# dual_encoder_i2c_revD.net
KiCad netlist of a schematic drawn in EAGLE
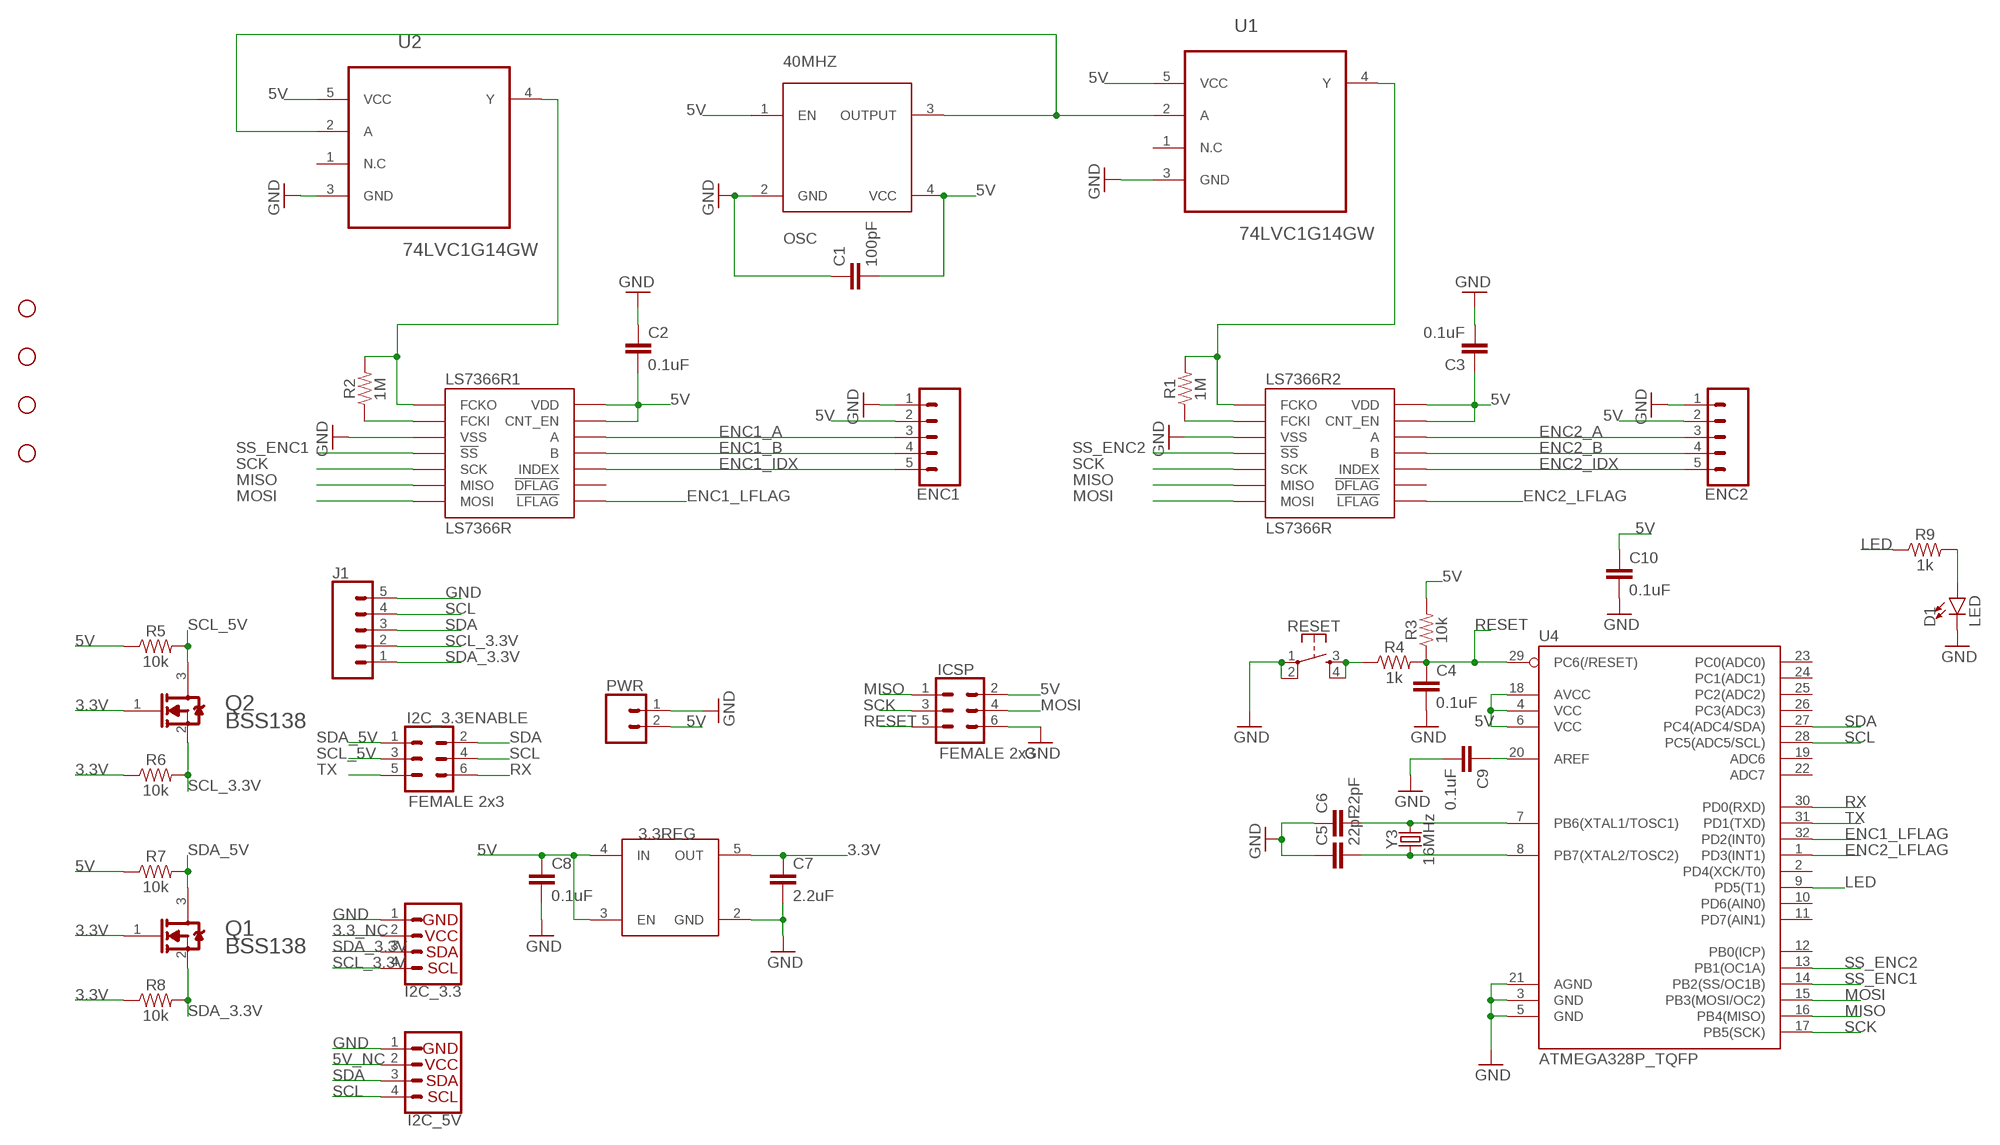
[diagram p0: schematic, sheet 1]

(export (version "E")
  (design (tool "Eeschema 10.0.6"))
  (components
    (comp (ref "3.3REG")
      (value "MIC3490-3.3YM5-TR")
      (footprint "eagle-import:SOT95P285X145-5N")
      (libsource (lib "eagle-import") (part "MIC3490-3.3YM5-TR"))
    )
    (comp (ref "40MHZ")
      (value "OSC")
      (footprint "eagle-import:CB3OSCILLATOR")
      (libsource (lib "eagle-import") (part "OSC"))
    )
    (comp (ref "C1")
      (value "100pF")
      (footprint "eagle-import:0603")
      (libsource (lib "eagle-import") (part "100PF-0603-50V-5%"))
    )
    (comp (ref "C2")
      (value "0.1uF")
      (footprint "eagle-import:0603")
      (libsource (lib "eagle-import") (part "0.1UF-0603-25V-5%"))
    )
    (comp (ref "C3")
      (value "0.1uF")
      (footprint "eagle-import:0603")
      (libsource (lib "eagle-import") (part "0.1UF-0603-25V-5%"))
    )
    (comp (ref "C4")
      (value "0.1uF")
      (footprint "eagle-import:0603")
      (libsource (lib "eagle-import") (part "0.1UF-0603-25V-5%"))
    )
    (comp (ref "C5")
      (value "22pF")
      (footprint "eagle-import:0603")
      (libsource (lib "eagle-import") (part "22PF-0603-50V-5%"))
    )
    (comp (ref "C6")
      (value "22pF")
      (footprint "eagle-import:0603")
      (libsource (lib "eagle-import") (part "22PF-0603-50V-5%"))
    )
    (comp (ref "C7")
      (value "2.2uF")
      (footprint "eagle-import:0603")
      (libsource (lib "eagle-import") (part "2.2UF-0603-10V-20%"))
    )
    (comp (ref "C8")
      (value "0.1uF")
      (footprint "eagle-import:0603")
      (libsource (lib "eagle-import") (part "0.1UF-0603-25V-5%"))
    )
    (comp (ref "C9")
      (value "0.1uF")
      (footprint "eagle-import:0603")
      (libsource (lib "eagle-import") (part "0.1UF-0603-25V-5%"))
    )
    (comp (ref "C10")
      (value "0.1uF")
      (footprint "eagle-import:0603")
      (libsource (lib "eagle-import") (part "0.1UF-0603-25V-5%"))
    )
    (comp (ref "D1")
      (value "LED")
      (footprint "eagle-import:LED-0603")
      (libsource (lib "eagle-import") (part "LED0603"))
    )
    (comp (ref "ENC1")
      (value "CONN_05")
      (footprint "eagle-import:1X05")
      (libsource (lib "eagle-import") (part "CONN_05"))
    )
    (comp (ref "ENC2")
      (value "CONN_05")
      (footprint "eagle-import:1X05")
      (libsource (lib "eagle-import") (part "CONN_05"))
    )
    (comp (ref "H1")
      (value "STAND-OFF")
      (footprint "eagle-import:STAND-OFF")
      (libsource (lib "eagle-import") (part "STAND-OFF"))
    )
    (comp (ref "H2")
      (value "STAND-OFF")
      (footprint "eagle-import:STAND-OFF")
      (libsource (lib "eagle-import") (part "STAND-OFF"))
    )
    (comp (ref "H3")
      (value "STAND-OFF")
      (footprint "eagle-import:STAND-OFF")
      (libsource (lib "eagle-import") (part "STAND-OFF"))
    )
    (comp (ref "H4")
      (value "STAND-OFF")
      (footprint "eagle-import:STAND-OFF")
      (libsource (lib "eagle-import") (part "STAND-OFF"))
    )
    (comp (ref "I2C_3.3")
      (value "QWIIC_CONNECTORJS-1MM")
      (footprint "eagle-import:JST04_1MM_RA")
      (libsource (lib "eagle-import") (part "QWIIC_CONNECTORJS-1MM"))
    )
    (comp (ref "I2C_3.3ENABLE")
      (value "FEMALE 2x3")
      (footprint "eagle-import:2X3")
      (libsource (lib "eagle-import") (part "CONN_03X2FEMALE"))
    )
    (comp (ref "I2C_5V")
      (value "QWIIC_CONNECTORJS-1MM")
      (footprint "eagle-import:JST04_1MM_RA")
      (libsource (lib "eagle-import") (part "QWIIC_CONNECTORJS-1MM"))
    )
    (comp (ref "ICSP")
      (value "FEMALE 2x3")
      (footprint "eagle-import:2X3")
      (libsource (lib "eagle-import") (part "CONN_03X2FEMALE"))
    )
    (comp (ref "J1")
      (value "CONN_05")
      (footprint "eagle-import:1X05")
      (libsource (lib "eagle-import") (part "CONN_05"))
    )
    (comp (ref "LS7366R1")
      (value "LS7366R")
      (footprint "eagle-import:SOIC14")
      (fields (field (name "MF") "LSI"))
      (libsource (lib "eagle-import") (part "LS7366R"))
    )
    (comp (ref "LS7366R2")
      (value "LS7366R")
      (footprint "eagle-import:SOIC14")
      (fields (field (name "MF") "LSI"))
      (libsource (lib "eagle-import") (part "LS7366R"))
    )
    (comp (ref "PWR")
      (value "CONN_02-JST-2MM-SMT")
      (footprint "eagle-import:JST-2-SMD")
      (libsource (lib "eagle-import") (part "CONN_02-JST-2MM-SMT"))
    )
    (comp (ref "Q1")
      (value "ON_SEMI_BSS138ON_SEMI_BSS138_0_0")
      (footprint "eagle-import:ON_SEMI_BSS138_0")
      (fields
        (field (name "DIGIKEY_PART_NUMBER") "BSS138CT-ND")
        (field (name "MF") "ON Semi")
        (field (name "MOUSER_PART_NUMBER") "512-BSS138")
      )
      (libsource (lib "eagle-import") (part "ON_SEMI_BSS138ON_SEMI_BSS138_0_0"))
    )
    (comp (ref "Q2")
      (value "ON_SEMI_BSS138ON_SEMI_BSS138_0_0")
      (footprint "eagle-import:ON_SEMI_BSS138_0")
      (fields
        (field (name "DIGIKEY_PART_NUMBER") "BSS138CT-ND")
        (field (name "MF") "ON Semi")
        (field (name "MOUSER_PART_NUMBER") "512-BSS138")
      )
      (libsource (lib "eagle-import") (part "ON_SEMI_BSS138ON_SEMI_BSS138_0_0"))
    )
    (comp (ref "R1")
      (value "1M")
      (footprint "eagle-import:0603")
      (libsource (lib "eagle-import") (part "1MOHM-0603-1/4W-5%"))
    )
    (comp (ref "R2")
      (value "1M")
      (footprint "eagle-import:0603")
      (libsource (lib "eagle-import") (part "1MOHM-0603-1/4W-5%"))
    )
    (comp (ref "R3")
      (value "10k")
      (footprint "eagle-import:0603")
      (libsource (lib "eagle-import") (part "10KOHM-0603-1/10W-1%"))
    )
    (comp (ref "R4")
      (value "1k")
      (footprint "eagle-import:0603")
      (libsource (lib "eagle-import") (part "1KOHM-0603-1/10W-1%"))
    )
    (comp (ref "R5")
      (value "10k")
      (footprint "eagle-import:0603")
      (libsource (lib "eagle-import") (part "10KOHM-0603-1/10W-1%"))
    )
    (comp (ref "R6")
      (value "10k")
      (footprint "eagle-import:0603")
      (libsource (lib "eagle-import") (part "10KOHM-0603-1/10W-1%"))
    )
    (comp (ref "R7")
      (value "10k")
      (footprint "eagle-import:0603")
      (libsource (lib "eagle-import") (part "10KOHM-0603-1/10W-1%"))
    )
    (comp (ref "R8")
      (value "10k")
      (footprint "eagle-import:0603")
      (libsource (lib "eagle-import") (part "10KOHM-0603-1/10W-1%"))
    )
    (comp (ref "R9")
      (value "1k")
      (footprint "eagle-import:0603")
      (libsource (lib "eagle-import") (part "1KOHM-0603-1/10W-1%"))
    )
    (comp (ref "RESET")
      (value "MOMENTARY-SWITCH-SPST-2-SMD-5.2MM")
      (footprint "eagle-import:TACTILE_SWITCH_SMD_5.2MM")
      (libsource (lib "eagle-import") (part "MOMENTARY-SWITCH-SPST-2-SMD-5.2MM"))
    )
    (comp (ref "U1")
      (value "74LVC1G14GW")
      (footprint "eagle-import:SOT65P210X110-5N")
      (fields (field (name "MF") "NXP Semiconductors"))
      (libsource (lib "eagle-import") (part "74LVC1G14GW"))
    )
    (comp (ref "U2")
      (value "74LVC1G14GW")
      (footprint "eagle-import:SOT65P210X110-5N")
      (fields (field (name "MF") "NXP Semiconductors"))
      (libsource (lib "eagle-import") (part "74LVC1G14GW"))
    )
    (comp (ref "U4")
      (value "ATMEGA328P_TQFP")
      (footprint "eagle-import:TQFP32-08")
      (libsource (lib "eagle-import") (part "ATMEGA328P_TQFP"))
    )
    (comp (ref "Y3")
      (value "16MHz")
      (footprint "eagle-import:CRYSTAL-SMD-5X3.2-4PAD")
      (libsource (lib "eagle-import") (part "CRYSTAL-16MHZSMD-5X3.2"))
    )
  )
  (nets
    (net (code "1") (name "/3.3V") (class "Default")
      (node (ref "3.3REG") (pin "5") (pinfunction "OUT_5") (pintype "output"))
      (node (ref "C7") (pin "1") (pinfunction "1_1") (pintype "passive"))
      (node (ref "Q1") (pin "1") (pinfunction "G_1") (pintype "bidirectional"))
      (node (ref "Q2") (pin "1") (pinfunction "G_1") (pintype "bidirectional"))
      (node (ref "R6") (pin "1") (pinfunction "1_1") (pintype "passive"))
      (node (ref "R8") (pin "1") (pinfunction "1_1") (pintype "passive"))
    )
    (net (code "2") (name "/3.3_NC") (class "Default")
      (node (ref "I2C_3.3") (pin "2") (pinfunction "2_2") (pintype "power_in"))
    )
    (net (code "3") (name "/5V") (class "Default")
      (node (ref "3.3REG") (pin "3") (pinfunction "EN_3") (pintype "input"))
      (node (ref "3.3REG") (pin "4") (pinfunction "IN_4") (pintype "input"))
      (node (ref "40MHZ") (pin "1") (pinfunction "EN_1") (pintype "input"))
      (node (ref "40MHZ") (pin "4") (pinfunction "VCC_4") (pintype "input"))
      (node (ref "C1") (pin "2") (pinfunction "2_2") (pintype "passive"))
      (node (ref "C10") (pin "1") (pinfunction "1_1") (pintype "passive"))
      (node (ref "C2") (pin "2") (pinfunction "2_2") (pintype "passive"))
      (node (ref "C3") (pin "1") (pinfunction "1_1") (pintype "passive"))
      (node (ref "C8") (pin "1") (pinfunction "1_1") (pintype "passive"))
      (node (ref "ENC1") (pin "2") (pinfunction "2_2") (pintype "passive"))
      (node (ref "ENC2") (pin "2") (pinfunction "2_2") (pintype "passive"))
      (node (ref "ICSP") (pin "2") (pinfunction "2_2") (pintype "bidirectional"))
      (node (ref "LS7366R1") (pin "13") (pinfunction "CNT_EN_13") (pintype "bidirectional"))
      (node (ref "LS7366R1") (pin "14") (pinfunction "VDD_14") (pintype "bidirectional"))
      (node (ref "LS7366R2") (pin "13") (pinfunction "CNT_EN_13") (pintype "bidirectional"))
      (node (ref "LS7366R2") (pin "14") (pinfunction "VDD_14") (pintype "bidirectional"))
      (node (ref "PWR") (pin "2") (pinfunction "1_2") (pintype "passive"))
      (node (ref "R3") (pin "2") (pinfunction "2_2") (pintype "passive"))
      (node (ref "R5") (pin "1") (pinfunction "1_1") (pintype "passive"))
      (node (ref "R7") (pin "1") (pinfunction "1_1") (pintype "passive"))
      (node (ref "U1") (pin "5") (pinfunction "VCC_5") (pintype "power_in"))
      (node (ref "U2") (pin "5") (pinfunction "VCC_5") (pintype "power_in"))
      (node (ref "U4") (pin "18") (pinfunction "AVCC_18") (pintype "bidirectional"))
      (node (ref "U4") (pin "4") (pinfunction "VCC_4") (pintype "bidirectional"))
      (node (ref "U4") (pin "6") (pinfunction "VCC_6") (pintype "bidirectional"))
    )
    (net (code "4") (name "/5V_NC") (class "Default")
      (node (ref "I2C_5V") (pin "2") (pinfunction "2_2") (pintype "power_in"))
    )
    (net (code "5") (name "/ENC1_A") (class "Default")
      (node (ref "ENC1") (pin "3") (pinfunction "3_3") (pintype "passive"))
      (node (ref "LS7366R1") (pin "12") (pinfunction "A_12") (pintype "bidirectional"))
    )
    (net (code "6") (name "/ENC1_B") (class "Default")
      (node (ref "ENC1") (pin "4") (pinfunction "4_4") (pintype "passive"))
      (node (ref "LS7366R1") (pin "11") (pinfunction "B_11") (pintype "bidirectional"))
    )
    (net (code "7") (name "/ENC1_IDX") (class "Default")
      (node (ref "ENC1") (pin "5") (pinfunction "5_5") (pintype "passive"))
      (node (ref "LS7366R1") (pin "10") (pinfunction "INDEX_10") (pintype "bidirectional"))
    )
    (net (code "8") (name "/ENC1_LFLAG") (class "Default")
      (node (ref "LS7366R1") (pin "8") (pinfunction "~{LFLAG}_8") (pintype "bidirectional"))
      (node (ref "U4") (pin "32") (pinfunction "PD2(INT0)_32") (pintype "bidirectional"))
    )
    (net (code "9") (name "/ENC2_A") (class "Default")
      (node (ref "ENC2") (pin "3") (pinfunction "3_3") (pintype "passive"))
      (node (ref "LS7366R2") (pin "12") (pinfunction "A_12") (pintype "bidirectional"))
    )
    (net (code "10") (name "/ENC2_B") (class "Default")
      (node (ref "ENC2") (pin "4") (pinfunction "4_4") (pintype "passive"))
      (node (ref "LS7366R2") (pin "11") (pinfunction "B_11") (pintype "bidirectional"))
    )
    (net (code "11") (name "/ENC2_IDX") (class "Default")
      (node (ref "ENC2") (pin "5") (pinfunction "5_5") (pintype "passive"))
      (node (ref "LS7366R2") (pin "10") (pinfunction "INDEX_10") (pintype "bidirectional"))
    )
    (net (code "12") (name "/ENC2_LFLAG") (class "Default")
      (node (ref "LS7366R2") (pin "8") (pinfunction "~{LFLAG}_8") (pintype "bidirectional"))
      (node (ref "U4") (pin "1") (pinfunction "PD3(INT1)_1") (pintype "bidirectional"))
    )
    (net (code "13") (name "/LED") (class "Default")
      (node (ref "R9") (pin "1") (pinfunction "1_1") (pintype "passive"))
      (node (ref "U4") (pin "9") (pinfunction "PD5(T1)_9") (pintype "bidirectional"))
    )
    (net (code "14") (name "/MISO") (class "Default")
      (node (ref "ICSP") (pin "1") (pinfunction "1_1") (pintype "bidirectional"))
      (node (ref "LS7366R1") (pin "6") (pinfunction "MISO_6") (pintype "bidirectional"))
      (node (ref "LS7366R2") (pin "6") (pinfunction "MISO_6") (pintype "bidirectional"))
      (node (ref "U4") (pin "16") (pinfunction "PB4(MISO)_16") (pintype "bidirectional"))
    )
    (net (code "15") (name "/MOSI") (class "Default")
      (node (ref "ICSP") (pin "4") (pinfunction "4_4") (pintype "bidirectional"))
      (node (ref "LS7366R1") (pin "7") (pinfunction "MOSI_7") (pintype "bidirectional"))
      (node (ref "LS7366R2") (pin "7") (pinfunction "MOSI_7") (pintype "bidirectional"))
      (node (ref "U4") (pin "15") (pinfunction "PB3(MOSI/OC2)_15") (pintype "bidirectional"))
    )
    (net (code "16") (name "/RESET") (class "Default")
      (node (ref "C4") (pin "1") (pinfunction "1_1") (pintype "passive"))
      (node (ref "ICSP") (pin "5") (pinfunction "5_5") (pintype "bidirectional"))
      (node (ref "R3") (pin "1") (pinfunction "1_1") (pintype "passive"))
      (node (ref "R4") (pin "2") (pinfunction "2_2") (pintype "passive"))
      (node (ref "U4") (pin "29") (pinfunction "PC6(/RESET)_29") (pintype "bidirectional"))
    )
    (net (code "17") (name "/RX") (class "Default")
      (node (ref "I2C_3.3ENABLE") (pin "6") (pinfunction "6_6") (pintype "bidirectional"))
      (node (ref "U4") (pin "30") (pinfunction "PD0(RXD)_30") (pintype "bidirectional"))
    )
    (net (code "18") (name "/SCK") (class "Default")
      (node (ref "ICSP") (pin "3") (pinfunction "3_3") (pintype "bidirectional"))
      (node (ref "LS7366R1") (pin "5") (pinfunction "SCK_5") (pintype "bidirectional"))
      (node (ref "LS7366R2") (pin "5") (pinfunction "SCK_5") (pintype "bidirectional"))
      (node (ref "U4") (pin "17") (pinfunction "PB5(SCK)_17") (pintype "bidirectional"))
    )
    (net (code "19") (name "/SCL") (class "Default")
      (node (ref "I2C_3.3ENABLE") (pin "4") (pinfunction "4_4") (pintype "bidirectional"))
      (node (ref "I2C_5V") (pin "4") (pinfunction "4_4") (pintype "passive"))
      (node (ref "J1") (pin "4") (pinfunction "4_4") (pintype "passive"))
      (node (ref "U4") (pin "28") (pinfunction "PC5(ADC5/SCL)_28") (pintype "bidirectional"))
    )
    (net (code "20") (name "/SCL_3.3V") (class "Default")
      (node (ref "I2C_3.3") (pin "4") (pinfunction "4_4") (pintype "passive"))
      (node (ref "J1") (pin "2") (pinfunction "2_2") (pintype "passive"))
      (node (ref "Q2") (pin "2") (pinfunction "S_2") (pintype "bidirectional"))
      (node (ref "R6") (pin "2") (pinfunction "2_2") (pintype "passive"))
    )
    (net (code "21") (name "/SCL_5V") (class "Default")
      (node (ref "I2C_3.3ENABLE") (pin "3") (pinfunction "3_3") (pintype "bidirectional"))
      (node (ref "Q2") (pin "3") (pinfunction "D_3") (pintype "bidirectional"))
      (node (ref "R5") (pin "2") (pinfunction "2_2") (pintype "passive"))
    )
    (net (code "22") (name "/SDA") (class "Default")
      (node (ref "I2C_3.3ENABLE") (pin "2") (pinfunction "2_2") (pintype "bidirectional"))
      (node (ref "I2C_5V") (pin "3") (pinfunction "3_3") (pintype "passive"))
      (node (ref "J1") (pin "3") (pinfunction "3_3") (pintype "passive"))
      (node (ref "U4") (pin "27") (pinfunction "PC4(ADC4/SDA)_27") (pintype "bidirectional"))
    )
    (net (code "23") (name "/SDA_3.3V") (class "Default")
      (node (ref "I2C_3.3") (pin "3") (pinfunction "3_3") (pintype "passive"))
      (node (ref "J1") (pin "1") (pinfunction "1_1") (pintype "passive"))
      (node (ref "Q1") (pin "2") (pinfunction "S_2") (pintype "bidirectional"))
      (node (ref "R8") (pin "2") (pinfunction "2_2") (pintype "passive"))
    )
    (net (code "24") (name "/SDA_5V") (class "Default")
      (node (ref "I2C_3.3ENABLE") (pin "1") (pinfunction "1_1") (pintype "bidirectional"))
      (node (ref "Q1") (pin "3") (pinfunction "D_3") (pintype "bidirectional"))
      (node (ref "R7") (pin "2") (pinfunction "2_2") (pintype "passive"))
    )
    (net (code "25") (name "/SS_ENC1") (class "Default")
      (node (ref "LS7366R1") (pin "4") (pinfunction "~{SS}_4") (pintype "bidirectional"))
      (node (ref "U4") (pin "14") (pinfunction "PB2(SS/OC1B)_14") (pintype "bidirectional"))
    )
    (net (code "26") (name "/SS_ENC2") (class "Default")
      (node (ref "LS7366R2") (pin "4") (pinfunction "~{SS}_4") (pintype "bidirectional"))
      (node (ref "U4") (pin "13") (pinfunction "PB1(OC1A)_13") (pintype "bidirectional"))
    )
    (net (code "27") (name "/TX") (class "Default")
      (node (ref "I2C_3.3ENABLE") (pin "5") (pinfunction "5_5") (pintype "bidirectional"))
      (node (ref "U4") (pin "31") (pinfunction "PD1(TXD)_31") (pintype "bidirectional"))
    )
    (net (code "28") (name "GND") (class "Default")
      (node (ref "3.3REG") (pin "2") (pinfunction "GND_2") (pintype "bidirectional"))
      (node (ref "40MHZ") (pin "2") (pinfunction "GND_2") (pintype "input"))
      (node (ref "C1") (pin "1") (pinfunction "1_1") (pintype "passive"))
      (node (ref "C10") (pin "2") (pinfunction "2_2") (pintype "passive"))
      (node (ref "C2") (pin "1") (pinfunction "1_1") (pintype "passive"))
      (node (ref "C3") (pin "2") (pinfunction "2_2") (pintype "passive"))
      (node (ref "C4") (pin "2") (pinfunction "2_2") (pintype "passive"))
      (node (ref "C5") (pin "1") (pinfunction "1_1") (pintype "passive"))
      (node (ref "C6") (pin "1") (pinfunction "1_1") (pintype "passive"))
      (node (ref "C7") (pin "2") (pinfunction "2_2") (pintype "passive"))
      (node (ref "C8") (pin "2") (pinfunction "2_2") (pintype "passive"))
      (node (ref "C9") (pin "2") (pinfunction "2_2") (pintype "passive"))
      (node (ref "D1") (pin "C") (pinfunction "C_C") (pintype "passive"))
      (node (ref "ENC1") (pin "1") (pinfunction "1_1") (pintype "passive"))
      (node (ref "ENC2") (pin "1") (pinfunction "1_1") (pintype "passive"))
      (node (ref "I2C_3.3") (pin "1") (pinfunction "1_1") (pintype "power_in"))
      (node (ref "I2C_5V") (pin "1") (pinfunction "1_1") (pintype "power_in"))
      (node (ref "ICSP") (pin "6") (pinfunction "6_6") (pintype "bidirectional"))
      (node (ref "J1") (pin "5") (pinfunction "5_5") (pintype "passive"))
      (node (ref "LS7366R1") (pin "3") (pinfunction "VSS_3") (pintype "bidirectional"))
      (node (ref "LS7366R2") (pin "3") (pinfunction "VSS_3") (pintype "bidirectional"))
      (node (ref "PWR") (pin "1") (pinfunction "2_1") (pintype "passive"))
      (node (ref "RESET") (pin "1") (pinfunction "1_1") (pintype "passive"))
      (node (ref "RESET") (pin "2") (pinfunction "2_2") (pintype "passive"))
      (node (ref "U1") (pin "3") (pinfunction "GND_3") (pintype "passive"))
      (node (ref "U2") (pin "3") (pinfunction "GND_3") (pintype "passive"))
      (node (ref "U4") (pin "21") (pinfunction "AGND_21") (pintype "bidirectional"))
      (node (ref "U4") (pin "3") (pinfunction "GND_3") (pintype "bidirectional"))
      (node (ref "U4") (pin "5") (pinfunction "GND_5") (pintype "bidirectional"))
    )
    (net (code "29") (name "Net-(40MHZ-OUTPUT)") (class "Default")
      (node (ref "40MHZ") (pin "3") (pinfunction "OUTPUT_3") (pintype "output"))
      (node (ref "U1") (pin "2") (pinfunction "A_2") (pintype "input"))
      (node (ref "U2") (pin "2") (pinfunction "A_2") (pintype "input"))
    )
    (net (code "30") (name "Net-(D1-PadA)") (class "Default")
      (node (ref "D1") (pin "A") (pinfunction "A_A") (pintype "passive"))
      (node (ref "R9") (pin "2") (pinfunction "2_2") (pintype "passive"))
    )
    (net (code "31") (name "Net-(LS7366R1-FCKI)") (class "Default")
      (node (ref "LS7366R1") (pin "2") (pinfunction "FCKI_2") (pintype "bidirectional"))
      (node (ref "R2") (pin "1") (pinfunction "1_1") (pintype "passive"))
    )
    (net (code "32") (name "Net-(LS7366R1-FCKO)") (class "Default")
      (node (ref "LS7366R1") (pin "1") (pinfunction "FCKO_1") (pintype "bidirectional"))
      (node (ref "R2") (pin "2") (pinfunction "2_2") (pintype "passive"))
      (node (ref "U2") (pin "4") (pinfunction "Y_4") (pintype "output"))
    )
    (net (code "33") (name "Net-(LS7366R2-FCKI)") (class "Default")
      (node (ref "LS7366R2") (pin "2") (pinfunction "FCKI_2") (pintype "bidirectional"))
      (node (ref "R1") (pin "1") (pinfunction "1_1") (pintype "passive"))
    )
    (net (code "34") (name "Net-(LS7366R2-FCKO)") (class "Default")
      (node (ref "LS7366R2") (pin "1") (pinfunction "FCKO_1") (pintype "bidirectional"))
      (node (ref "R1") (pin "2") (pinfunction "2_2") (pintype "passive"))
      (node (ref "U1") (pin "4") (pinfunction "Y_4") (pintype "output"))
    )
    (net (code "35") (name "Net-(R4-Pad1)") (class "Default")
      (node (ref "R4") (pin "1") (pinfunction "1_1") (pintype "passive"))
      (node (ref "RESET") (pin "3") (pinfunction "3_3") (pintype "passive"))
      (node (ref "RESET") (pin "4") (pinfunction "4_4") (pintype "passive"))
    )
    (net (code "36") (name "Net-(U4-AREF)") (class "Default")
      (node (ref "C9") (pin "1") (pinfunction "1_1") (pintype "passive"))
      (node (ref "U4") (pin "20") (pinfunction "AREF_20") (pintype "bidirectional"))
    )
    (net (code "37") (name "Net-(U4-PB6(XTAL1{slash}TOSC1))") (class "Default")
      (node (ref "C6") (pin "2") (pinfunction "2_2") (pintype "passive"))
      (node (ref "U4") (pin "7") (pinfunction "PB6(XTAL1/TOSC1)_7") (pintype "bidirectional"))
      (node (ref "Y3") (pin "3") (pinfunction "2_3") (pintype "passive"))
    )
    (net (code "38") (name "Net-(U4-PB7(XTAL2{slash}TOSC2))") (class "Default")
      (node (ref "C5") (pin "2") (pinfunction "2_2") (pintype "passive"))
      (node (ref "U4") (pin "8") (pinfunction "PB7(XTAL2/TOSC2)_8") (pintype "bidirectional"))
      (node (ref "Y3") (pin "1") (pinfunction "1_1") (pintype "passive"))
    )
    (net (code "39") (name "unconnected-(LS7366R1-~{DFLAG}-Pad9)") (class "Default")
      (node (ref "LS7366R1") (pin "9") (pinfunction "~{DFLAG}_9") (pintype "bidirectional"))
    )
    (net (code "40") (name "unconnected-(LS7366R2-~{DFLAG}-Pad9)") (class "Default")
      (node (ref "LS7366R2") (pin "9") (pinfunction "~{DFLAG}_9") (pintype "bidirectional"))
    )
    (net (code "41") (name "unconnected-(U1-N.C-Pad1)") (class "Default")
      (node (ref "U1") (pin "1") (pinfunction "N.C_1") (pintype "no_connect"))
    )
    (net (code "42") (name "unconnected-(U2-N.C-Pad1)") (class "Default")
      (node (ref "U2") (pin "1") (pinfunction "N.C_1") (pintype "no_connect"))
    )
    (net (code "43") (name "unconnected-(U4-ADC6-Pad19)") (class "Default")
      (node (ref "U4") (pin "19") (pinfunction "ADC6_19") (pintype "bidirectional"))
    )
    (net (code "44") (name "unconnected-(U4-ADC7-Pad22)") (class "Default")
      (node (ref "U4") (pin "22") (pinfunction "ADC7_22") (pintype "bidirectional"))
    )
    (net (code "45") (name "unconnected-(U4-PB0(ICP)-Pad12)") (class "Default")
      (node (ref "U4") (pin "12") (pinfunction "PB0(ICP)_12") (pintype "bidirectional"))
    )
    (net (code "46") (name "unconnected-(U4-PC0(ADC0)-Pad23)") (class "Default")
      (node (ref "U4") (pin "23") (pinfunction "PC0(ADC0)_23") (pintype "bidirectional"))
    )
    (net (code "47") (name "unconnected-(U4-PC1(ADC1)-Pad24)") (class "Default")
      (node (ref "U4") (pin "24") (pinfunction "PC1(ADC1)_24") (pintype "bidirectional"))
    )
    (net (code "48") (name "unconnected-(U4-PC2(ADC2)-Pad25)") (class "Default")
      (node (ref "U4") (pin "25") (pinfunction "PC2(ADC2)_25") (pintype "bidirectional"))
    )
    (net (code "49") (name "unconnected-(U4-PC3(ADC3)-Pad26)") (class "Default")
      (node (ref "U4") (pin "26") (pinfunction "PC3(ADC3)_26") (pintype "bidirectional"))
    )
    (net (code "50") (name "unconnected-(U4-PD4(XCK{slash}T0)-Pad2)") (class "Default")
      (node (ref "U4") (pin "2") (pinfunction "PD4(XCK/T0)_2") (pintype "bidirectional"))
    )
    (net (code "51") (name "unconnected-(U4-PD6(AIN0)-Pad10)") (class "Default")
      (node (ref "U4") (pin "10") (pinfunction "PD6(AIN0)_10") (pintype "bidirectional"))
    )
    (net (code "52") (name "unconnected-(U4-PD7(AIN1)-Pad11)") (class "Default")
      (node (ref "U4") (pin "11") (pinfunction "PD7(AIN1)_11") (pintype "bidirectional"))
    )
  )
)
